# babyGroot.net
KiCad netlist of a schematic drawn in EAGLE
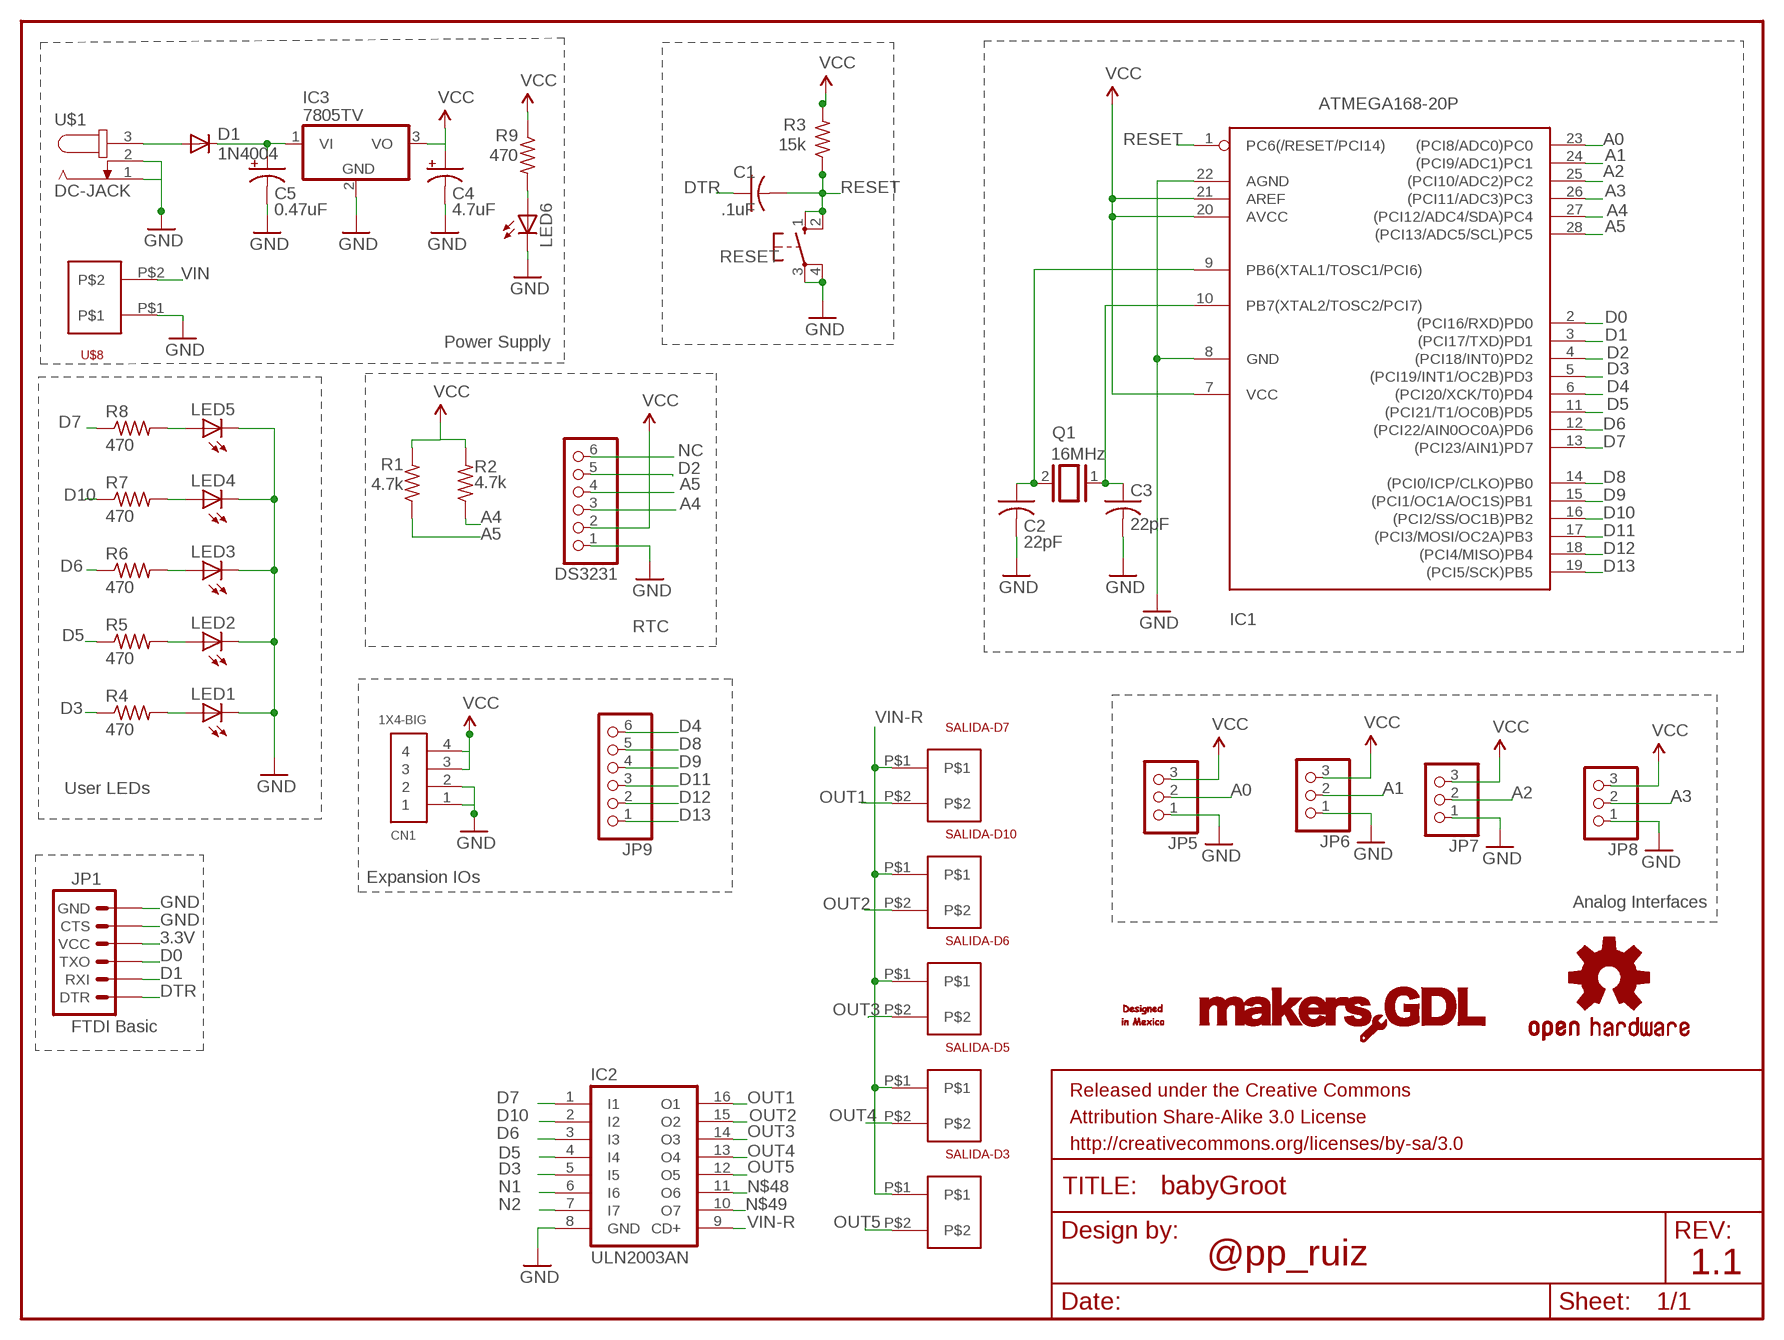
[diagram p0: schematic, sheet 1]

(export (version "E")
  (design (tool "Eeschema 10.0.6"))
  (components
    (comp (ref "C1")
      (value ".1uF")
      (footprint "eagle-import:C025-024X044")
      (libsource (lib "eagle-import") (part "C-US025-024X044"))
    )
    (comp (ref "C2")
      (value "22pF")
      (footprint "eagle-import:C025-024X044")
      (libsource (lib "eagle-import") (part "C-US025-024X044"))
    )
    (comp (ref "C3")
      (value "22pF")
      (footprint "eagle-import:C025-024X044")
      (libsource (lib "eagle-import") (part "C-US025-024X044"))
    )
    (comp (ref "C4")
      (value "4.7uF")
      (footprint "eagle-import:E2,5-6E")
      (libsource (lib "eagle-import") (part "CPOL-USE2,5-6E"))
    )
    (comp (ref "C5")
      (value "0.47uF")
      (footprint "eagle-import:E2,5-6E")
      (libsource (lib "eagle-import") (part "CPOL-USE2,5-6E"))
    )
    (comp (ref "CN1")
      (value "1X4-BIG")
      (footprint "eagle-import:1X04-BIG")
      (libsource (lib "eagle-import") (part "1X4-BIG"))
    )
    (comp (ref "D1")
      (value "1N4004")
      (footprint "eagle-import:DO41-10")
      (libsource (lib "eagle-import") (part "1N4004"))
    )
    (comp (ref "DS3231")
      (value "PINHD-1X6")
      (footprint "eagle-import:1X06")
      (libsource (lib "eagle-import") (part "PINHD-1X6"))
    )
    (comp (ref "FRAME1")
      (value "FRAME-LETTER")
      (footprint "eagle-import:CREATIVE_COMMONS")
      (libsource (lib "eagle-import") (part "FRAME-LETTER"))
    )
    (comp (ref "IC1")
      (value "ATMEGA168-20P")
      (footprint "eagle-import:DIL28-3")
      (libsource (lib "eagle-import") (part "ATMEGA168P-20"))
    )
    (comp (ref "IC2")
      (value "ULN2003AN")
      (footprint "eagle-import:DIL16")
      (libsource (lib "eagle-import") (part "ULN2003AN"))
    )
    (comp (ref "IC3")
      (value "7805TV")
      (footprint "eagle-import:TO220V")
      (libsource (lib "eagle-import") (part "78TV05"))
    )
    (comp (ref "JP1")
      (value "FTDI Basic")
      (footprint "eagle-import:1X06")
      (libsource (lib "eagle-import") (part "ARDUINO_SERIAL_PROGRAMPTH"))
    )
    (comp (ref "JP5")
      (value "PINHD-1X3")
      (footprint "eagle-import:1X03")
      (libsource (lib "eagle-import") (part "PINHD-1X3"))
    )
    (comp (ref "JP6")
      (value "PINHD-1X3")
      (footprint "eagle-import:1X03")
      (libsource (lib "eagle-import") (part "PINHD-1X3"))
    )
    (comp (ref "JP7")
      (value "PINHD-1X3")
      (footprint "eagle-import:1X03")
      (libsource (lib "eagle-import") (part "PINHD-1X3"))
    )
    (comp (ref "JP8")
      (value "PINHD-1X3")
      (footprint "eagle-import:1X03")
      (libsource (lib "eagle-import") (part "PINHD-1X3"))
    )
    (comp (ref "JP9")
      (value "PINHD-1X6")
      (footprint "eagle-import:1X06")
      (libsource (lib "eagle-import") (part "PINHD-1X6"))
    )
    (comp (ref "LED1")
      (value "LED3MM")
      (footprint "eagle-import:LED3MM")
      (libsource (lib "eagle-import") (part "LED3MM"))
    )
    (comp (ref "LED2")
      (value "LED3MM")
      (footprint "eagle-import:LED3MM")
      (libsource (lib "eagle-import") (part "LED3MM"))
    )
    (comp (ref "LED3")
      (value "LED3MM")
      (footprint "eagle-import:LED3MM")
      (libsource (lib "eagle-import") (part "LED3MM"))
    )
    (comp (ref "LED4")
      (value "LED3MM")
      (footprint "eagle-import:LED3MM")
      (libsource (lib "eagle-import") (part "LED3MM"))
    )
    (comp (ref "LED5")
      (value "LED3MM")
      (footprint "eagle-import:LED3MM")
      (libsource (lib "eagle-import") (part "LED3MM"))
    )
    (comp (ref "LED6")
      (value "LED3MM")
      (footprint "eagle-import:LED3MM")
      (libsource (lib "eagle-import") (part "LED3MM"))
    )
    (comp (ref "Q1")
      (value "16MHz")
      (footprint "eagle-import:QS")
      (libsource (lib "eagle-import") (part "XTAL/S"))
    )
    (comp (ref "R1")
      (value "4.7k")
      (footprint "eagle-import:0204V")
      (libsource (lib "eagle-import") (part "R-US_0204/2V"))
    )
    (comp (ref "R2")
      (value "4.7k")
      (footprint "eagle-import:0204V")
      (libsource (lib "eagle-import") (part "R-US_0204/2V"))
    )
    (comp (ref "R3")
      (value "15k")
      (footprint "eagle-import:0204V")
      (libsource (lib "eagle-import") (part "R-US_0204/2V"))
    )
    (comp (ref "R4")
      (value "470")
      (footprint "eagle-import:0204V")
      (libsource (lib "eagle-import") (part "R-US_0204/2V"))
    )
    (comp (ref "R5")
      (value "470")
      (footprint "eagle-import:0204V")
      (libsource (lib "eagle-import") (part "R-US_0204/2V"))
    )
    (comp (ref "R6")
      (value "470")
      (footprint "eagle-import:0204V")
      (libsource (lib "eagle-import") (part "R-US_0204/2V"))
    )
    (comp (ref "R7")
      (value "470")
      (footprint "eagle-import:0204V")
      (libsource (lib "eagle-import") (part "R-US_0204/2V"))
    )
    (comp (ref "R8")
      (value "470")
      (footprint "eagle-import:0204V")
      (libsource (lib "eagle-import") (part "R-US_0204/2V"))
    )
    (comp (ref "R9")
      (value "470")
      (footprint "eagle-import:0204V")
      (libsource (lib "eagle-import") (part "R-US_0204/2V"))
    )
    (comp (ref "RESET")
      (value "10-XX")
      (footprint "eagle-import:B3F-10XX")
      (fields (field (name "MPN") "B3F-1000"))
      (libsource (lib "eagle-import") (part "10-XX"))
    )
    (comp (ref "SALIDA-D3")
      (value "2POSHEADER-0.5MM")
      (footprint "eagle-import:2PIN-0.5MM")
      (libsource (lib "eagle-import") (part "2POSHEADER-0.5MM"))
    )
    (comp (ref "SALIDA-D5")
      (value "2POSHEADER-0.5MM")
      (footprint "eagle-import:2PIN-0.5MM")
      (libsource (lib "eagle-import") (part "2POSHEADER-0.5MM"))
    )
    (comp (ref "SALIDA-D6")
      (value "2POSHEADER-0.5MM")
      (footprint "eagle-import:2PIN-0.5MM")
      (libsource (lib "eagle-import") (part "2POSHEADER-0.5MM"))
    )
    (comp (ref "SALIDA-D7")
      (value "2POSHEADER-0.5MM")
      (footprint "eagle-import:2PIN-0.5MM")
      (libsource (lib "eagle-import") (part "2POSHEADER-0.5MM"))
    )
    (comp (ref "SALIDA-D10")
      (value "2POSHEADER-0.5MM")
      (footprint "eagle-import:2PIN-0.5MM")
      (libsource (lib "eagle-import") (part "2POSHEADER-0.5MM"))
    )
    (comp (ref "U$1")
      (value "DC-JACK")
      (footprint "eagle-import:SPC4078")
      (libsource (lib "eagle-import") (part "DC-JACK"))
    )
    (comp (ref "U$2")
      (value "MAKERSGDLLOGO-SMALL")
      (footprint "eagle-import:MAKERSGGL-SMALL")
      (libsource (lib "eagle-import") (part "MAKERSGDLLOGO-SMALL"))
    )
    (comp (ref "U$3")
      (value "OSHW-LOGOS")
      (footprint "eagle-import:OSHW-LOGO-S")
      (libsource (lib "eagle-import") (part "OSHW-LOGOS"))
    )
    (comp (ref "U$4")
      (value "MAKERSGDLLOGO-SMALL")
      (footprint "eagle-import:MAKERSGGL-SMALL")
      (libsource (lib "eagle-import") (part "MAKERSGDLLOGO-SMALL"))
    )
    (comp (ref "U$5")
      (value "OSHW-LOGOS")
      (footprint "eagle-import:OSHW-LOGO-S")
      (libsource (lib "eagle-import") (part "OSHW-LOGOS"))
    )
    (comp (ref "U$6")
      (value "DESIGNEDMEXICO")
      (footprint "eagle-import:DESIGNEDMEXICO")
      (libsource (lib "eagle-import") (part "DESIGNEDMEXICO"))
    )
    (comp (ref "U$8")
      (value "2POSHEADER-0.5MM")
      (footprint "eagle-import:2PIN-0.5MM")
      (libsource (lib "eagle-import") (part "2POSHEADER-0.5MM"))
    )
  )
  (nets
    (net (code "1") (name "/A0") (class "Default")
      (node (ref "IC1") (pin "23") (pinfunction "(PCI8/ADC0)PC0_23") (pintype "bidirectional"))
      (node (ref "JP5") (pin "2") (pinfunction "2_2") (pintype "passive"))
    )
    (net (code "2") (name "/A1") (class "Default")
      (node (ref "IC1") (pin "24") (pinfunction "(PCI9/ADC1)PC1_24") (pintype "bidirectional"))
      (node (ref "JP6") (pin "2") (pinfunction "2_2") (pintype "passive"))
    )
    (net (code "3") (name "/A2") (class "Default")
      (node (ref "IC1") (pin "25") (pinfunction "(PCI10/ADC2)PC2_25") (pintype "bidirectional"))
      (node (ref "JP7") (pin "2") (pinfunction "2_2") (pintype "passive"))
    )
    (net (code "4") (name "/A3") (class "Default")
      (node (ref "IC1") (pin "26") (pinfunction "(PCI11/ADC3)PC3_26") (pintype "bidirectional"))
      (node (ref "JP8") (pin "2") (pinfunction "2_2") (pintype "passive"))
    )
    (net (code "5") (name "/A4") (class "Default")
      (node (ref "DS3231") (pin "3") (pinfunction "3_3") (pintype "passive"))
      (node (ref "IC1") (pin "27") (pinfunction "(PCI12/ADC4/SDA)PC4_27") (pintype "bidirectional"))
      (node (ref "R2") (pin "1") (pinfunction "1_1") (pintype "passive"))
    )
    (net (code "6") (name "/A5") (class "Default")
      (node (ref "DS3231") (pin "4") (pinfunction "4_4") (pintype "passive"))
      (node (ref "IC1") (pin "28") (pinfunction "(PCI13/ADC5/SCL)PC5_28") (pintype "bidirectional"))
      (node (ref "R1") (pin "1") (pinfunction "1_1") (pintype "passive"))
    )
    (net (code "7") (name "/D0") (class "Default")
      (node (ref "IC1") (pin "2") (pinfunction "(PCI16/RXD)PD0_2") (pintype "bidirectional"))
      (node (ref "JP1") (pin "3") (pinfunction "TXO_3") (pintype "passive"))
    )
    (net (code "8") (name "/D1") (class "Default")
      (node (ref "IC1") (pin "3") (pinfunction "(PCI17/TXD)PD1_3") (pintype "bidirectional"))
      (node (ref "JP1") (pin "2") (pinfunction "RXI_2") (pintype "passive"))
    )
    (net (code "9") (name "/D2") (class "Default")
      (node (ref "DS3231") (pin "5") (pinfunction "5_5") (pintype "passive"))
      (node (ref "IC1") (pin "4") (pinfunction "(PCI18/INT0)PD2_4") (pintype "bidirectional"))
    )
    (net (code "10") (name "/D3") (class "Default")
      (node (ref "IC1") (pin "5") (pinfunction "(PCI19/INT1/OC2B)PD3_5") (pintype "bidirectional"))
      (node (ref "IC2") (pin "5") (pinfunction "I5_5") (pintype "input"))
      (node (ref "R4") (pin "1") (pinfunction "1_1") (pintype "passive"))
    )
    (net (code "11") (name "/D4") (class "Default")
      (node (ref "IC1") (pin "6") (pinfunction "(PCI20/XCK/T0)PD4_6") (pintype "bidirectional"))
      (node (ref "JP9") (pin "6") (pinfunction "6_6") (pintype "passive"))
    )
    (net (code "12") (name "/D5") (class "Default")
      (node (ref "IC1") (pin "11") (pinfunction "(PCI21/T1/OC0B)PD5_11") (pintype "bidirectional"))
      (node (ref "IC2") (pin "4") (pinfunction "I4_4") (pintype "input"))
      (node (ref "R5") (pin "1") (pinfunction "1_1") (pintype "passive"))
    )
    (net (code "13") (name "/D6") (class "Default")
      (node (ref "IC1") (pin "12") (pinfunction "(PCI22/AIN0OC0A)PD6_12") (pintype "bidirectional"))
      (node (ref "IC2") (pin "3") (pinfunction "I3_3") (pintype "input"))
      (node (ref "R6") (pin "1") (pinfunction "1_1") (pintype "passive"))
    )
    (net (code "14") (name "/D7") (class "Default")
      (node (ref "IC1") (pin "13") (pinfunction "(PCI23/AIN1)PD7_13") (pintype "bidirectional"))
      (node (ref "IC2") (pin "1") (pinfunction "I1_1") (pintype "input"))
      (node (ref "R8") (pin "1") (pinfunction "1_1") (pintype "passive"))
    )
    (net (code "15") (name "/D8") (class "Default")
      (node (ref "IC1") (pin "14") (pinfunction "(PCI0/ICP/CLKO)PB0_14") (pintype "bidirectional"))
      (node (ref "JP9") (pin "5") (pinfunction "5_5") (pintype "passive"))
    )
    (net (code "16") (name "/D9") (class "Default")
      (node (ref "IC1") (pin "15") (pinfunction "(PCI1/OC1A/OC1S)PB1_15") (pintype "bidirectional"))
      (node (ref "JP9") (pin "4") (pinfunction "4_4") (pintype "passive"))
    )
    (net (code "17") (name "/D10") (class "Default")
      (node (ref "IC1") (pin "16") (pinfunction "(PCI2/SS/OC1B)PB2_16") (pintype "bidirectional"))
      (node (ref "IC2") (pin "2") (pinfunction "I2_2") (pintype "input"))
      (node (ref "R7") (pin "1") (pinfunction "1_1") (pintype "passive"))
    )
    (net (code "18") (name "/D11") (class "Default")
      (node (ref "IC1") (pin "17") (pinfunction "(PCI3/MOSI/OC2A)PB3_17") (pintype "bidirectional"))
      (node (ref "JP9") (pin "3") (pinfunction "3_3") (pintype "passive"))
    )
    (net (code "19") (name "/D12") (class "Default")
      (node (ref "IC1") (pin "18") (pinfunction "(PCI4/MISO)PB4_18") (pintype "bidirectional"))
      (node (ref "JP9") (pin "2") (pinfunction "2_2") (pintype "passive"))
    )
    (net (code "20") (name "/D13") (class "Default")
      (node (ref "IC1") (pin "19") (pinfunction "(PCI5/SCK)PB5_19") (pintype "bidirectional"))
      (node (ref "JP9") (pin "1") (pinfunction "1_1") (pintype "passive"))
    )
    (net (code "21") (name "/DTR") (class "Default")
      (node (ref "C1") (pin "1") (pinfunction "1_1") (pintype "passive"))
      (node (ref "JP1") (pin "1") (pinfunction "DTR_1") (pintype "passive"))
    )
    (net (code "22") (name "/N$48") (class "Default")
      (node (ref "IC2") (pin "11") (pinfunction "O6_11") (pintype "open_collector"))
    )
    (net (code "23") (name "/N$49") (class "Default")
      (node (ref "IC2") (pin "10") (pinfunction "O7_10") (pintype "open_collector"))
    )
    (net (code "24") (name "/N1") (class "Default")
      (node (ref "IC2") (pin "6") (pinfunction "I6_6") (pintype "input"))
    )
    (net (code "25") (name "/N2") (class "Default")
      (node (ref "IC2") (pin "7") (pinfunction "I7_7") (pintype "input"))
    )
    (net (code "26") (name "/NC") (class "Default")
      (node (ref "DS3231") (pin "6") (pinfunction "6_6") (pintype "passive"))
    )
    (net (code "27") (name "/OUT1") (class "Default")
      (node (ref "IC2") (pin "16") (pinfunction "O1_16") (pintype "open_collector"))
      (node (ref "SALIDA-D7") (pin "P$2") (pinfunction "P$2_P$2") (pintype "bidirectional"))
    )
    (net (code "28") (name "/OUT2") (class "Default")
      (node (ref "IC2") (pin "15") (pinfunction "O2_15") (pintype "open_collector"))
      (node (ref "SALIDA-D10") (pin "P$2") (pinfunction "P$2_P$2") (pintype "bidirectional"))
    )
    (net (code "29") (name "/OUT3") (class "Default")
      (node (ref "IC2") (pin "14") (pinfunction "O3_14") (pintype "open_collector"))
      (node (ref "SALIDA-D6") (pin "P$2") (pinfunction "P$2_P$2") (pintype "bidirectional"))
    )
    (net (code "30") (name "/OUT4") (class "Default")
      (node (ref "IC2") (pin "13") (pinfunction "O4_13") (pintype "open_collector"))
      (node (ref "SALIDA-D5") (pin "P$2") (pinfunction "P$2_P$2") (pintype "bidirectional"))
    )
    (net (code "31") (name "/OUT5") (class "Default")
      (node (ref "IC2") (pin "12") (pinfunction "O5_12") (pintype "open_collector"))
      (node (ref "SALIDA-D3") (pin "P$2") (pinfunction "P$2_P$2") (pintype "bidirectional"))
    )
    (net (code "32") (name "/RESET") (class "Default")
      (node (ref "C1") (pin "2") (pinfunction "2_2") (pintype "passive"))
      (node (ref "IC1") (pin "1") (pinfunction "PC6(/RESET/PCI14)_1") (pintype "bidirectional"))
      (node (ref "R3") (pin "1") (pinfunction "1_1") (pintype "passive"))
      (node (ref "RESET") (pin "1") (pinfunction "S_1") (pintype "passive"))
      (node (ref "RESET") (pin "2") (pinfunction "S1_2") (pintype "passive"))
    )
    (net (code "33") (name "/VIN") (class "Default")
      (node (ref "D1") (pin "A") (pinfunction "A_A") (pintype "passive"))
      (node (ref "U$1") (pin "3") (pinfunction "3_3") (pintype "passive"))
      (node (ref "U$8") (pin "P$2") (pinfunction "P$2_P$2") (pintype "bidirectional"))
    )
    (net (code "34") (name "/VIN-R") (class "Default")
      (node (ref "C5") (pin "+") (pinfunction "+_+") (pintype "passive"))
      (node (ref "D1") (pin "C") (pinfunction "C_C") (pintype "passive"))
      (node (ref "IC2") (pin "9") (pinfunction "CD+_9") (pintype "passive"))
      (node (ref "IC3") (pin "1") (pinfunction "VI_1") (pintype "input"))
      (node (ref "SALIDA-D10") (pin "P$1") (pinfunction "P$1_P$1") (pintype "bidirectional"))
      (node (ref "SALIDA-D3") (pin "P$1") (pinfunction "P$1_P$1") (pintype "bidirectional"))
      (node (ref "SALIDA-D5") (pin "P$1") (pinfunction "P$1_P$1") (pintype "bidirectional"))
      (node (ref "SALIDA-D6") (pin "P$1") (pinfunction "P$1_P$1") (pintype "bidirectional"))
      (node (ref "SALIDA-D7") (pin "P$1") (pinfunction "P$1_P$1") (pintype "bidirectional"))
    )
    (net (code "35") (name "GND") (class "Default")
      (node (ref "C2") (pin "2") (pinfunction "2_2") (pintype "passive"))
      (node (ref "C3") (pin "2") (pinfunction "2_2") (pintype "passive"))
      (node (ref "C4") (pin "-") (pinfunction "-_-") (pintype "passive"))
      (node (ref "C5") (pin "-") (pinfunction "-_-") (pintype "passive"))
      (node (ref "CN1") (pin "1") (pinfunction "1_1") (pintype "bidirectional"))
      (node (ref "CN1") (pin "2") (pinfunction "2_2") (pintype "bidirectional"))
      (node (ref "DS3231") (pin "1") (pinfunction "1_1") (pintype "passive"))
      (node (ref "IC1") (pin "22") (pinfunction "AGND_22") (pintype "bidirectional"))
      (node (ref "IC1") (pin "8") (pinfunction "GND_8") (pintype "bidirectional"))
      (node (ref "IC2") (pin "8") (pinfunction "GND_8") (pintype "power_in"))
      (node (ref "IC3") (pin "2") (pinfunction "GND_2") (pintype "passive"))
      (node (ref "JP1") (pin "5") (pinfunction "CTS_5") (pintype "passive"))
      (node (ref "JP1") (pin "6") (pinfunction "GND_6") (pintype "passive"))
      (node (ref "JP5") (pin "1") (pinfunction "1_1") (pintype "passive"))
      (node (ref "JP6") (pin "1") (pinfunction "1_1") (pintype "passive"))
      (node (ref "JP7") (pin "1") (pinfunction "1_1") (pintype "passive"))
      (node (ref "JP8") (pin "1") (pinfunction "1_1") (pintype "passive"))
      (node (ref "LED1") (pin "K") (pinfunction "C_K") (pintype "passive"))
      (node (ref "LED2") (pin "K") (pinfunction "C_K") (pintype "passive"))
      (node (ref "LED3") (pin "K") (pinfunction "C_K") (pintype "passive"))
      (node (ref "LED4") (pin "K") (pinfunction "C_K") (pintype "passive"))
      (node (ref "LED5") (pin "K") (pinfunction "C_K") (pintype "passive"))
      (node (ref "LED6") (pin "K") (pinfunction "C_K") (pintype "passive"))
      (node (ref "RESET") (pin "3") (pinfunction "P_3") (pintype "passive"))
      (node (ref "RESET") (pin "4") (pinfunction "P1_4") (pintype "passive"))
      (node (ref "U$1") (pin "1") (pinfunction "1_1") (pintype "passive"))
      (node (ref "U$1") (pin "2") (pinfunction "2_2") (pintype "passive"))
      (node (ref "U$8") (pin "P$1") (pinfunction "P$1_P$1") (pintype "bidirectional"))
    )
    (net (code "36") (name "Net-(IC1-PB6(XTAL1{slash}TOSC1{slash}PCI6))") (class "Default")
      (node (ref "C2") (pin "1") (pinfunction "1_1") (pintype "passive"))
      (node (ref "IC1") (pin "9") (pinfunction "PB6(XTAL1/TOSC1/PCI6)_9") (pintype "bidirectional"))
      (node (ref "Q1") (pin "2") (pinfunction "2_2") (pintype "passive"))
    )
    (net (code "37") (name "Net-(IC1-PB7(XTAL2{slash}TOSC2{slash}PCI7))") (class "Default")
      (node (ref "C3") (pin "1") (pinfunction "1_1") (pintype "passive"))
      (node (ref "IC1") (pin "10") (pinfunction "PB7(XTAL2/TOSC2/PCI7)_10") (pintype "bidirectional"))
      (node (ref "Q1") (pin "1") (pinfunction "1_1") (pintype "passive"))
    )
    (net (code "38") (name "Net-(LED1-PadA)") (class "Default")
      (node (ref "LED1") (pin "A") (pinfunction "A_A") (pintype "passive"))
      (node (ref "R4") (pin "2") (pinfunction "2_2") (pintype "passive"))
    )
    (net (code "39") (name "Net-(LED2-PadA)") (class "Default")
      (node (ref "LED2") (pin "A") (pinfunction "A_A") (pintype "passive"))
      (node (ref "R5") (pin "2") (pinfunction "2_2") (pintype "passive"))
    )
    (net (code "40") (name "Net-(LED3-PadA)") (class "Default")
      (node (ref "LED3") (pin "A") (pinfunction "A_A") (pintype "passive"))
      (node (ref "R6") (pin "2") (pinfunction "2_2") (pintype "passive"))
    )
    (net (code "41") (name "Net-(LED4-PadA)") (class "Default")
      (node (ref "LED4") (pin "A") (pinfunction "A_A") (pintype "passive"))
      (node (ref "R7") (pin "2") (pinfunction "2_2") (pintype "passive"))
    )
    (net (code "42") (name "Net-(LED5-PadA)") (class "Default")
      (node (ref "LED5") (pin "A") (pinfunction "A_A") (pintype "passive"))
      (node (ref "R8") (pin "2") (pinfunction "2_2") (pintype "passive"))
    )
    (net (code "43") (name "Net-(LED6-PadA)") (class "Default")
      (node (ref "LED6") (pin "A") (pinfunction "A_A") (pintype "passive"))
      (node (ref "R9") (pin "2") (pinfunction "2_2") (pintype "passive"))
    )
    (net (code "44") (name "VCC") (class "Default")
      (node (ref "C4") (pin "+") (pinfunction "+_+") (pintype "passive"))
      (node (ref "CN1") (pin "3") (pinfunction "3_3") (pintype "bidirectional"))
      (node (ref "CN1") (pin "4") (pinfunction "4_4") (pintype "bidirectional"))
      (node (ref "DS3231") (pin "2") (pinfunction "2_2") (pintype "passive"))
      (node (ref "IC1") (pin "20") (pinfunction "AVCC_20") (pintype "bidirectional"))
      (node (ref "IC1") (pin "21") (pinfunction "AREF_21") (pintype "bidirectional"))
      (node (ref "IC1") (pin "7") (pinfunction "VCC_7") (pintype "bidirectional"))
      (node (ref "IC3") (pin "3") (pinfunction "VO_3") (pintype "passive"))
      (node (ref "JP1") (pin "4") (pinfunction "VCC_4") (pintype "passive"))
      (node (ref "JP5") (pin "3") (pinfunction "3_3") (pintype "passive"))
      (node (ref "JP6") (pin "3") (pinfunction "3_3") (pintype "passive"))
      (node (ref "JP7") (pin "3") (pinfunction "3_3") (pintype "passive"))
      (node (ref "JP8") (pin "3") (pinfunction "3_3") (pintype "passive"))
      (node (ref "R1") (pin "2") (pinfunction "2_2") (pintype "passive"))
      (node (ref "R2") (pin "2") (pinfunction "2_2") (pintype "passive"))
      (node (ref "R3") (pin "2") (pinfunction "2_2") (pintype "passive"))
      (node (ref "R9") (pin "1") (pinfunction "1_1") (pintype "passive"))
    )
  )
)
